# adcdac.net
KiCad netlist of a schematic drawn in EAGLE
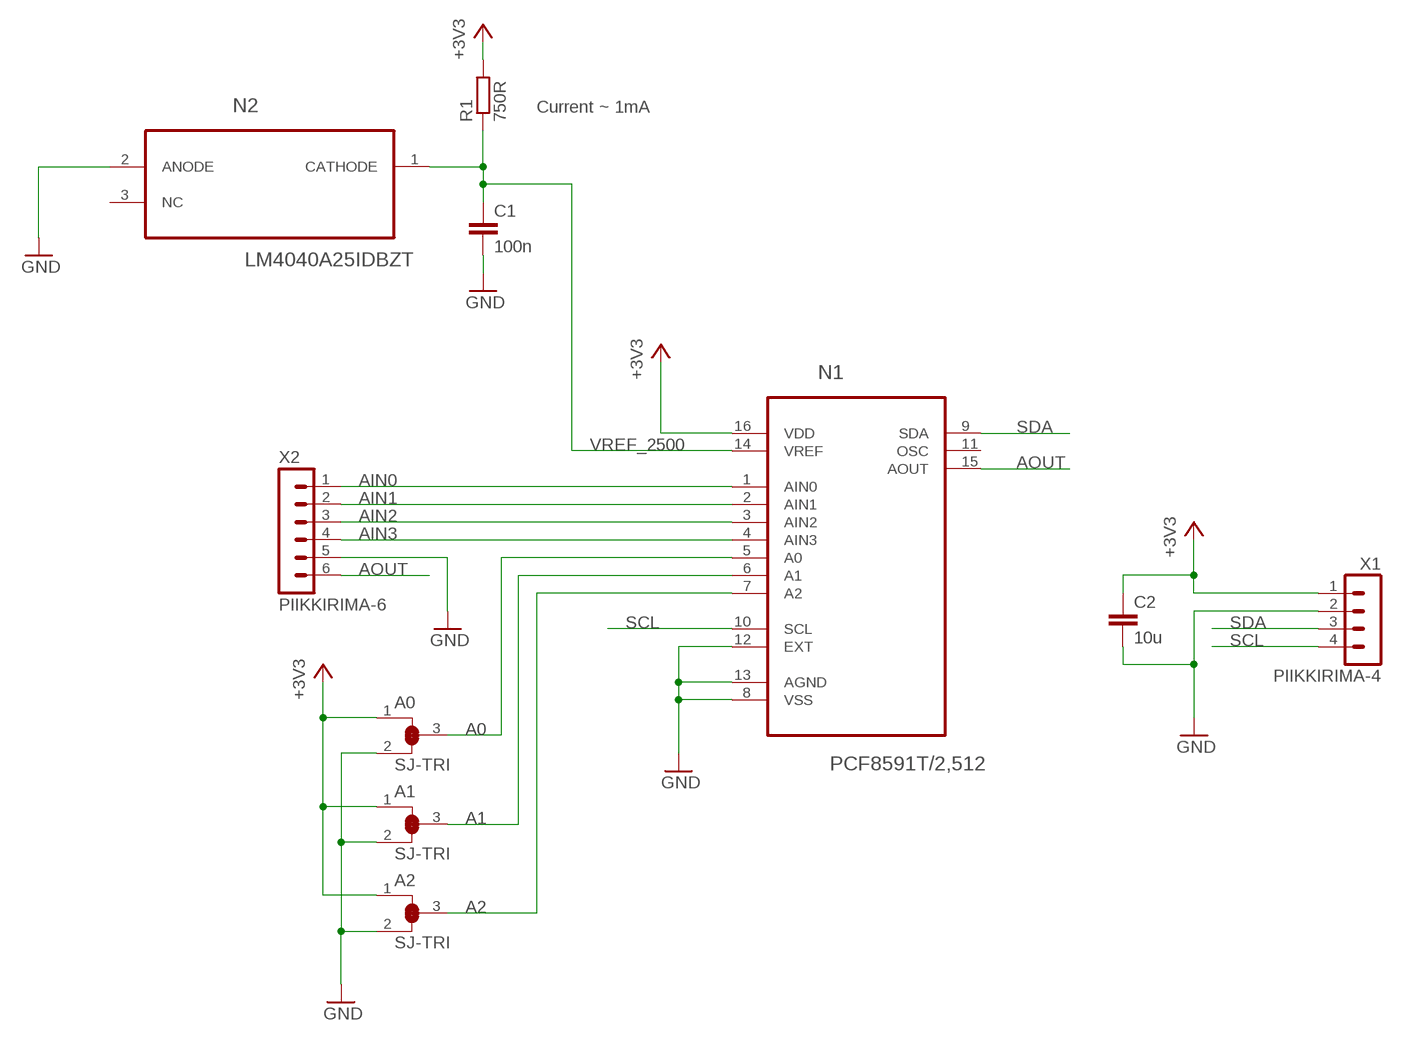
[diagram p0: schematic, sheet 1]

(export (version "E")
  (design (tool "Eeschema 10.0.6"))
  (components
    (comp (ref "A0")
      (value "SJ-TRI")
      (footprint "eagle-import:SJ-SMALL-TRI")
      (libsource (lib "eagle-import") (part "SJ-TRI"))
    )
    (comp (ref "A1")
      (value "SJ-TRI")
      (footprint "eagle-import:SJ-SMALL-TRI")
      (libsource (lib "eagle-import") (part "SJ-TRI"))
    )
    (comp (ref "A2")
      (value "SJ-TRI")
      (footprint "eagle-import:SJ-SMALL-TRI")
      (libsource (lib "eagle-import") (part "SJ-TRI"))
    )
    (comp (ref "C1")
      (value "100n")
      (footprint "eagle-import:C0603")
      (libsource (lib "eagle-import") (part "C-EUC0603"))
    )
    (comp (ref "C2")
      (value "10u")
      (footprint "eagle-import:C0805")
      (libsource (lib "eagle-import") (part "C-EUC0805"))
    )
    (comp (ref "N1")
      (value "PCF8591T/2,512")
      (footprint "eagle-import:SOIC127P1032X265-16N")
      (libsource (lib "eagle-import") (part "PCF8591T/2,512"))
    )
    (comp (ref "N2")
      (value "LM4040A25IDBZT")
      (footprint "eagle-import:SOT95P237X112-3N")
      (libsource (lib "eagle-import") (part "LM4040A25IDBZT"))
    )
    (comp (ref "R1")
      (value "750R")
      (footprint "eagle-import:R0603")
      (libsource (lib "eagle-import") (part "R-EU_R0603"))
    )
    (comp (ref "X1")
      (value "PIIKKIRIMA-4")
      (footprint "eagle-import:PIIKKIRIMA-4")
      (libsource (lib "eagle-import") (part "PIIKKIRIMA-4"))
    )
    (comp (ref "X2")
      (value "PIIKKIRIMA-6")
      (footprint "eagle-import:PIIKKIRIMA-6")
      (libsource (lib "eagle-import") (part "PIIKKIRIMA-6"))
    )
  )
  (nets
    (net (code "1") (name "+3V3") (class "Default")
      (node (ref "A0") (pin "1") (pinfunction "1_1") (pintype "passive"))
      (node (ref "A1") (pin "1") (pinfunction "1_1") (pintype "passive"))
      (node (ref "A2") (pin "1") (pinfunction "1_1") (pintype "passive"))
      (node (ref "C2") (pin "1") (pinfunction "1_1") (pintype "passive"))
      (node (ref "N1") (pin "16") (pinfunction "VDD_16") (pintype "power_in"))
      (node (ref "R1") (pin "2") (pinfunction "2_2") (pintype "passive"))
      (node (ref "X1") (pin "1") (pinfunction "1_1") (pintype "passive"))
    )
    (net (code "2") (name "/A0") (class "Default")
      (node (ref "A0") (pin "3") (pinfunction "3_3") (pintype "passive"))
      (node (ref "N1") (pin "5") (pinfunction "A0_5") (pintype "input"))
    )
    (net (code "3") (name "/A1") (class "Default")
      (node (ref "A1") (pin "3") (pinfunction "3_3") (pintype "passive"))
      (node (ref "N1") (pin "6") (pinfunction "A1_6") (pintype "input"))
    )
    (net (code "4") (name "/A2") (class "Default")
      (node (ref "A2") (pin "3") (pinfunction "3_3") (pintype "passive"))
      (node (ref "N1") (pin "7") (pinfunction "A2_7") (pintype "input"))
    )
    (net (code "5") (name "/AIN0") (class "Default")
      (node (ref "N1") (pin "1") (pinfunction "AIN0_1") (pintype "input"))
      (node (ref "X2") (pin "1") (pinfunction "1_1") (pintype "passive"))
    )
    (net (code "6") (name "/AIN1") (class "Default")
      (node (ref "N1") (pin "2") (pinfunction "AIN1_2") (pintype "input"))
      (node (ref "X2") (pin "2") (pinfunction "2_2") (pintype "passive"))
    )
    (net (code "7") (name "/AIN2") (class "Default")
      (node (ref "N1") (pin "3") (pinfunction "AIN2_3") (pintype "input"))
      (node (ref "X2") (pin "3") (pinfunction "3_3") (pintype "passive"))
    )
    (net (code "8") (name "/AIN3") (class "Default")
      (node (ref "N1") (pin "4") (pinfunction "AIN3_4") (pintype "input"))
      (node (ref "X2") (pin "4") (pinfunction "4_4") (pintype "passive"))
    )
    (net (code "9") (name "/AOUT") (class "Default")
      (node (ref "N1") (pin "15") (pinfunction "AOUT_15") (pintype "output"))
      (node (ref "X2") (pin "6") (pinfunction "6_6") (pintype "passive"))
    )
    (net (code "10") (name "/SCL") (class "Default")
      (node (ref "N1") (pin "10") (pinfunction "SCL_10") (pintype "input"))
      (node (ref "X1") (pin "4") (pinfunction "4_4") (pintype "passive"))
    )
    (net (code "11") (name "/SDA") (class "Default")
      (node (ref "N1") (pin "9") (pinfunction "SDA_9") (pintype "bidirectional"))
      (node (ref "X1") (pin "3") (pinfunction "3_3") (pintype "passive"))
    )
    (net (code "12") (name "/VREF_2500") (class "Default")
      (node (ref "C1") (pin "1") (pinfunction "1_1") (pintype "passive"))
      (node (ref "N1") (pin "14") (pinfunction "VREF_14") (pintype "input"))
      (node (ref "N2") (pin "1") (pinfunction "CATHODE_1") (pintype "output"))
      (node (ref "R1") (pin "1") (pinfunction "1_1") (pintype "passive"))
    )
    (net (code "13") (name "GND") (class "Default")
      (node (ref "A0") (pin "2") (pinfunction "2_2") (pintype "passive"))
      (node (ref "A1") (pin "2") (pinfunction "2_2") (pintype "passive"))
      (node (ref "A2") (pin "2") (pinfunction "2_2") (pintype "passive"))
      (node (ref "C1") (pin "2") (pinfunction "2_2") (pintype "passive"))
      (node (ref "C2") (pin "2") (pinfunction "2_2") (pintype "passive"))
      (node (ref "N1") (pin "12") (pinfunction "EXT_12") (pintype "passive"))
      (node (ref "N1") (pin "13") (pinfunction "AGND_13") (pintype "passive"))
      (node (ref "N1") (pin "8") (pinfunction "VSS_8") (pintype "power_in"))
      (node (ref "N2") (pin "2") (pinfunction "ANODE_2") (pintype "input"))
      (node (ref "X1") (pin "2") (pinfunction "2_2") (pintype "passive"))
      (node (ref "X2") (pin "5") (pinfunction "5_5") (pintype "passive"))
    )
    (net (code "14") (name "unconnected-(N1-OSC-Pad11)") (class "Default")
      (node (ref "N1") (pin "11") (pinfunction "OSC_11") (pintype "bidirectional"))
    )
    (net (code "15") (name "unconnected-(N2-NC-Pad3)") (class "Default")
      (node (ref "N2") (pin "3") (pinfunction "NC_3") (pintype "no_connect"))
    )
  )
)
